# BW1098OAK_TopLevel.net
KiCad netlist of a schematic drawn in Altium Designer
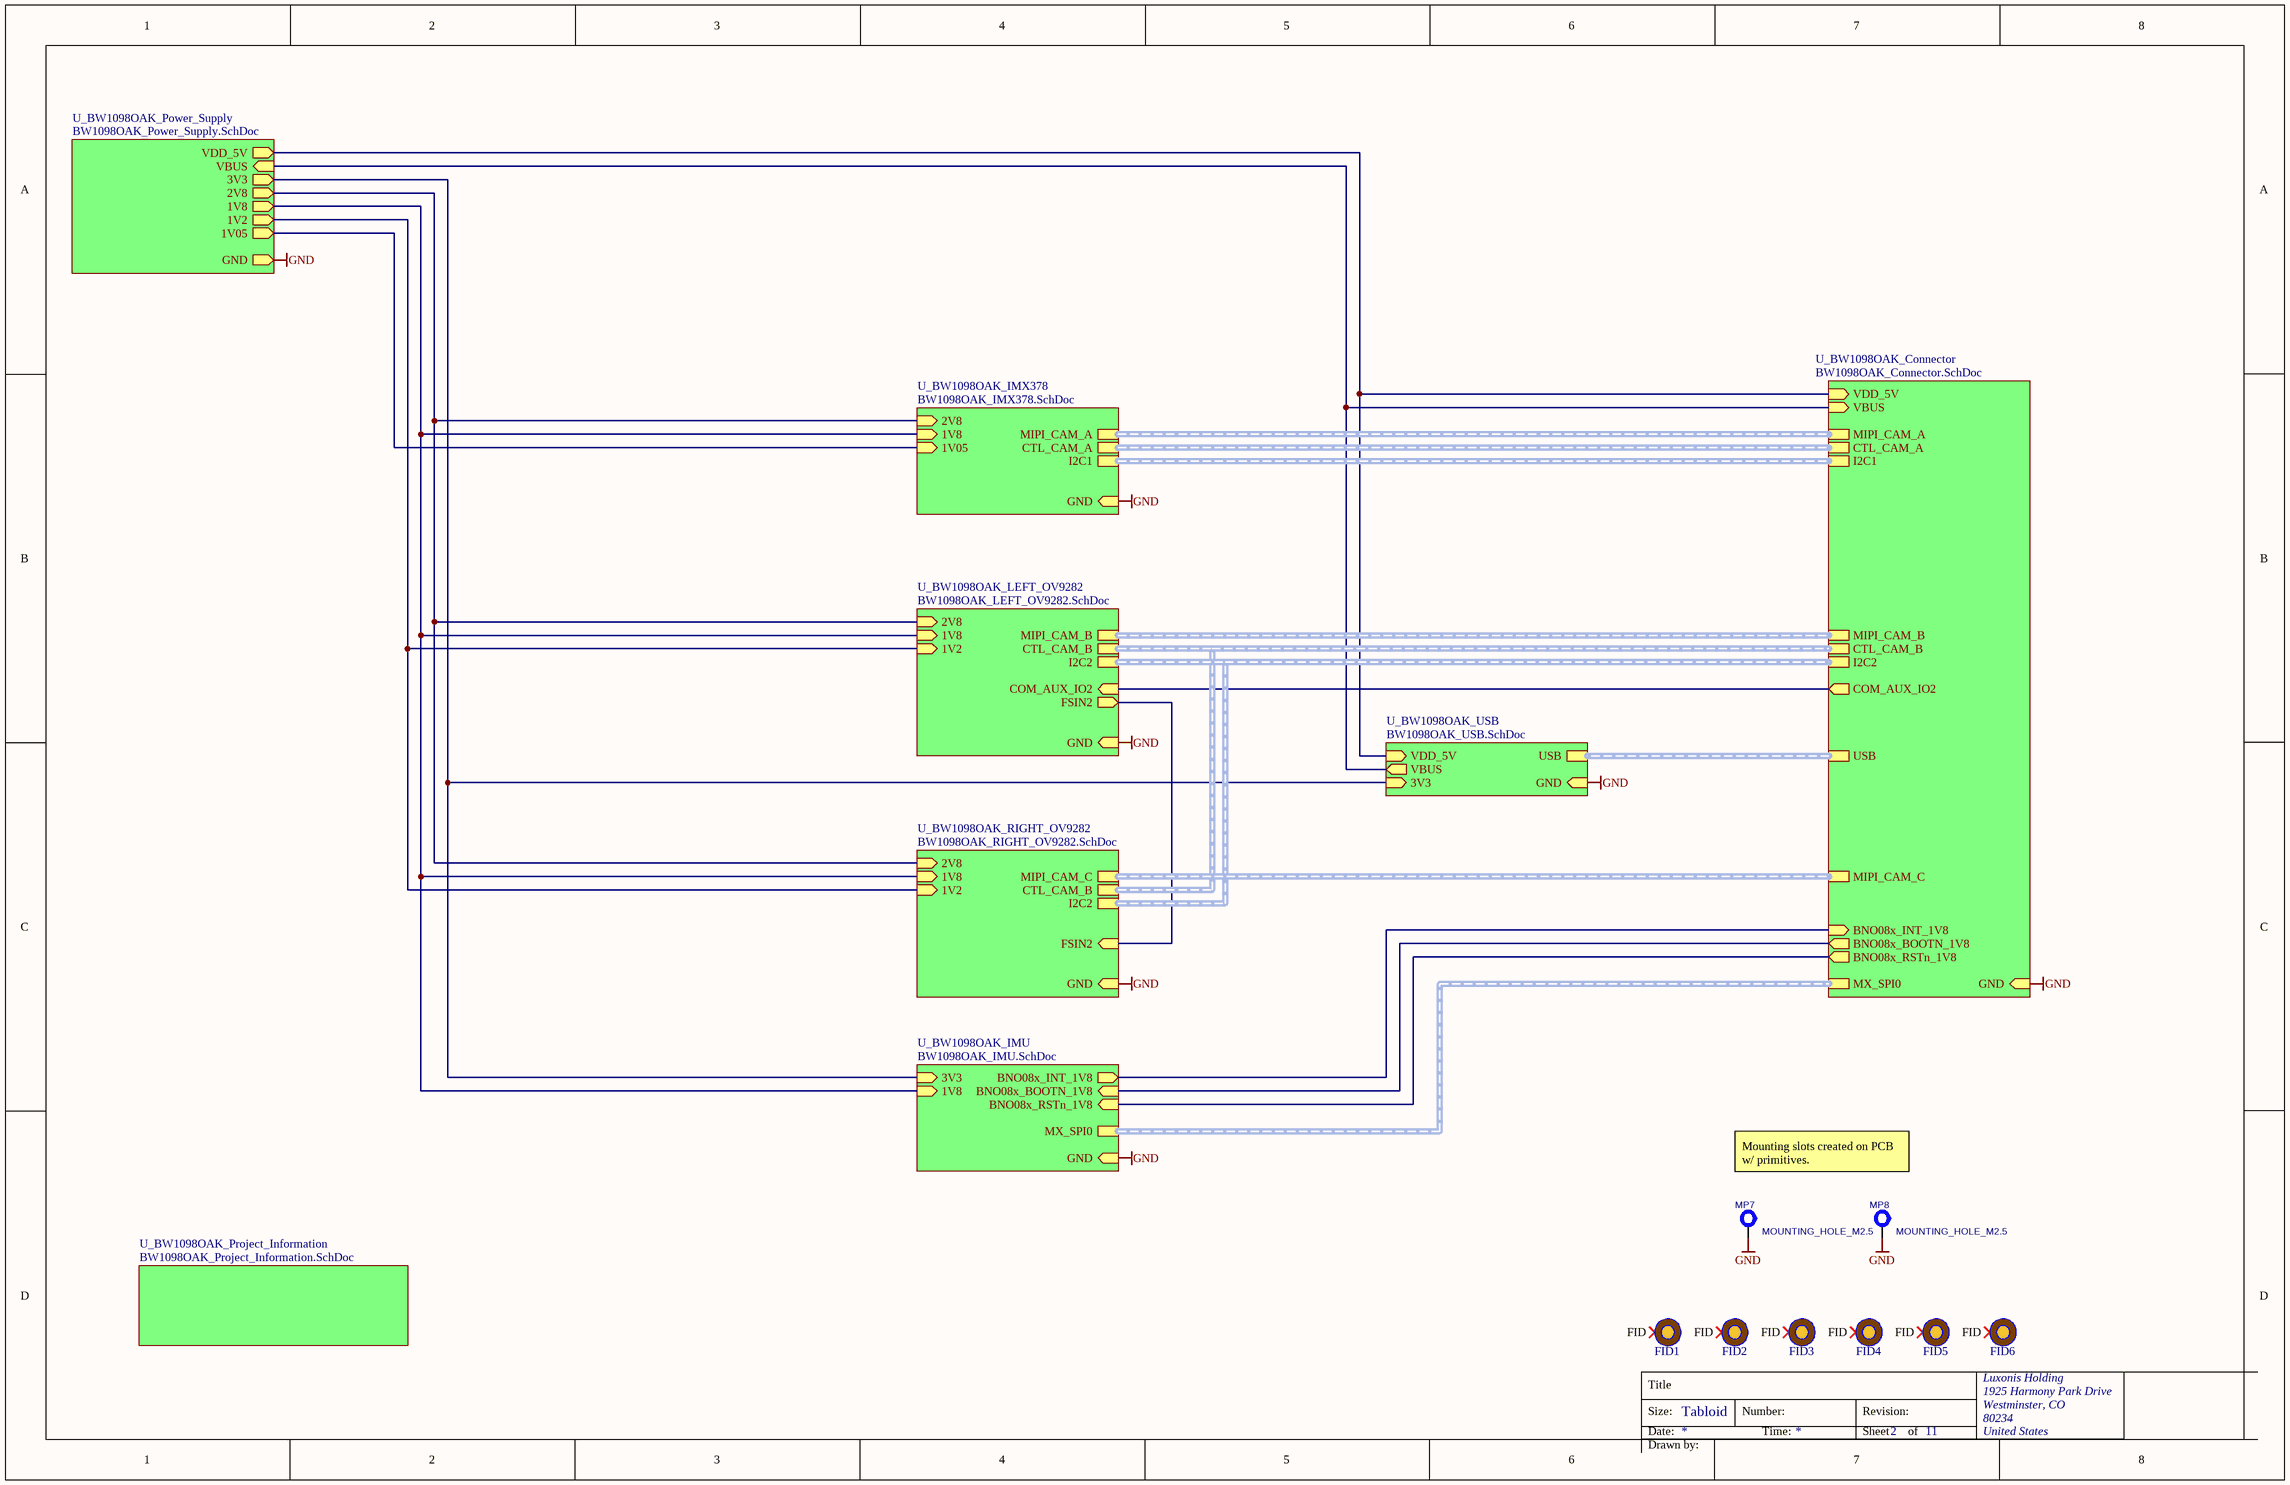
[diagram p0: BW1098OAK_TopLevel.SchDoc]

(export (version "E")
  (design (tool "Eeschema 10.0.6"))
  (components
    (comp (ref "FID1")
      (value "FIDUCIAL_ROUND_1MM")
      (footprint "LuxonisMaster:FIDUCIAL_ROUND_1MM")
      (description "Fiducial with various available footprints")
      (libsource (lib "LuxonisMaster") (part "FIDUCIAL"))
    )
    (comp (ref "FID2")
      (value "FIDUCIAL_ROUND_1MM")
      (footprint "LuxonisMaster:FIDUCIAL_ROUND_1MM")
      (description "Fiducial with various available footprints")
      (libsource (lib "LuxonisMaster") (part "FIDUCIAL"))
    )
    (comp (ref "FID3")
      (value "FIDUCIAL_ROUND_1MM")
      (footprint "LuxonisMaster:FIDUCIAL_ROUND_1MM")
      (description "Fiducial with various available footprints")
      (libsource (lib "LuxonisMaster") (part "FIDUCIAL"))
    )
    (comp (ref "FID4")
      (value "FIDUCIAL_ROUND_1MM")
      (footprint "LuxonisMaster:FIDUCIAL_ROUND_1MM")
      (description "Fiducial with various available footprints")
      (libsource (lib "LuxonisMaster") (part "FIDUCIAL"))
    )
    (comp (ref "FID5")
      (value "FIDUCIAL_ROUND_1MM")
      (footprint "LuxonisMaster:FIDUCIAL_ROUND_1MM")
      (description "Fiducial with various available footprints")
      (libsource (lib "LuxonisMaster") (part "FIDUCIAL"))
    )
    (comp (ref "FID6")
      (value "FIDUCIAL_ROUND_1MM")
      (footprint "LuxonisMaster:FIDUCIAL_ROUND_1MM")
      (description "Fiducial with various available footprints")
      (libsource (lib "LuxonisMaster") (part "FIDUCIAL"))
    )
    (comp (ref "MP7")
      (value "MOUNTING_HOLE_M2.5")
      (footprint "LuxonisMaster:MOUNTING_HOLE_M2.5")
      (description "=CurrentFootprint")
      (libsource (lib "LuxonisMaster") (part "MP_Mounting-Holes"))
    )
    (comp (ref "MP8")
      (value "MOUNTING_HOLE_M2.5")
      (footprint "LuxonisMaster:MOUNTING_HOLE_M2.5")
      (description "=CurrentFootprint")
      (libsource (lib "LuxonisMaster") (part "MP_Mounting-Holes"))
    )
  )
  (nets
    (net (code "22") (name "GND") (class "Default")
      (node (ref "MP7") (pin "1") (pintype "passive"))
      (node (ref "MP8") (pin "1") (pintype "passive"))
    )
    (net (code "23") (name "unconnected-(FID1-PadFID)") (class "Default")
      (node (ref "FID1") (pin "FID") (pinfunction "FID_FID") (pintype "input+no_connect"))
    )
    (net (code "24") (name "unconnected-(FID2-PadFID)") (class "Default")
      (node (ref "FID2") (pin "FID") (pinfunction "FID_FID") (pintype "input+no_connect"))
    )
    (net (code "25") (name "unconnected-(FID3-PadFID)") (class "Default")
      (node (ref "FID3") (pin "FID") (pinfunction "FID_FID") (pintype "input+no_connect"))
    )
    (net (code "26") (name "unconnected-(FID4-PadFID)") (class "Default")
      (node (ref "FID4") (pin "FID") (pinfunction "FID_FID") (pintype "input+no_connect"))
    )
    (net (code "27") (name "unconnected-(FID5-PadFID)") (class "Default")
      (node (ref "FID5") (pin "FID") (pinfunction "FID_FID") (pintype "input+no_connect"))
    )
    (net (code "28") (name "unconnected-(FID6-PadFID)") (class "Default")
      (node (ref "FID6") (pin "FID") (pinfunction "FID_FID") (pintype "input+no_connect"))
    )
  )
)
